# Slider.net
KiCad netlist of a schematic drawn in Altium Designer
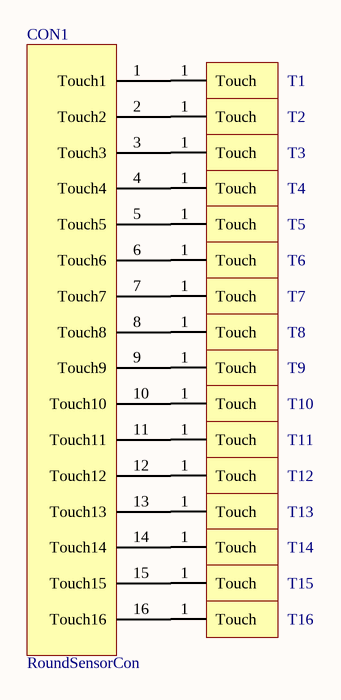
[diagram p0: Slider.SchDoc]

(export (version "E")
  (design (tool "Eeschema 10.0.6"))
  (components
    (comp (ref "CON1")
      (value "RoundSensorCon")
      (footprint "RoundSensorCon")
      (libsource (lib "RoundSensorCon") (part "RoundSensorCon"))
    )
    (comp (ref "T1") (value "Touch") (footprint "TOUCH") (libsource (lib "Touch") (part "Touch")))
    (comp (ref "T2") (value "Touch") (footprint "TOUCH") (libsource (lib "Touch") (part "Touch")))
    (comp (ref "T3") (value "Touch") (footprint "TOUCH") (libsource (lib "Touch") (part "Touch")))
    (comp (ref "T4") (value "Touch") (footprint "TOUCH") (libsource (lib "Touch") (part "Touch")))
    (comp (ref "T5") (value "Touch") (footprint "TOUCH") (libsource (lib "Touch") (part "Touch")))
    (comp (ref "T6") (value "Touch") (footprint "TOUCH") (libsource (lib "Touch") (part "Touch")))
    (comp (ref "T7") (value "Touch") (footprint "TOUCH") (libsource (lib "Touch") (part "Touch")))
    (comp (ref "T8") (value "Touch") (footprint "TOUCH") (libsource (lib "Touch") (part "Touch")))
    (comp (ref "T9") (value "Touch") (footprint "TOUCH") (libsource (lib "Touch") (part "Touch")))
    (comp (ref "T10") (value "Touch") (footprint "TOUCH") (libsource (lib "Touch") (part "Touch")))
    (comp (ref "T11") (value "Touch") (footprint "TOUCH") (libsource (lib "Touch") (part "Touch")))
    (comp (ref "T12") (value "Touch") (footprint "TOUCH") (libsource (lib "Touch") (part "Touch")))
    (comp (ref "T13") (value "Touch") (footprint "TOUCH") (libsource (lib "Touch") (part "Touch")))
    (comp (ref "T14") (value "Touch") (footprint "TOUCH") (libsource (lib "Touch") (part "Touch")))
    (comp (ref "T15") (value "Touch") (footprint "TOUCH") (libsource (lib "Touch") (part "Touch")))
    (comp (ref "T16") (value "Touch") (footprint "TOUCH") (libsource (lib "Touch") (part "Touch")))
  )
  (nets
    (net (code "1") (name "Net-(CON1-Touch1)") (class "Default")
      (node (ref "CON1") (pin "1") (pinfunction "Touch1_1") (pintype "passive"))
      (node (ref "T1") (pin "1") (pinfunction "Touch_1") (pintype "passive"))
    )
    (net (code "2") (name "Net-(CON1-Touch2)") (class "Default")
      (node (ref "CON1") (pin "2") (pinfunction "Touch2_2") (pintype "passive"))
      (node (ref "T2") (pin "1") (pinfunction "Touch_1") (pintype "passive"))
    )
    (net (code "3") (name "Net-(CON1-Touch3)") (class "Default")
      (node (ref "CON1") (pin "3") (pinfunction "Touch3_3") (pintype "passive"))
      (node (ref "T3") (pin "1") (pinfunction "Touch_1") (pintype "passive"))
    )
    (net (code "4") (name "Net-(CON1-Touch4)") (class "Default")
      (node (ref "CON1") (pin "4") (pinfunction "Touch4_4") (pintype "passive"))
      (node (ref "T4") (pin "1") (pinfunction "Touch_1") (pintype "passive"))
    )
    (net (code "5") (name "Net-(CON1-Touch5)") (class "Default")
      (node (ref "CON1") (pin "5") (pinfunction "Touch5_5") (pintype "passive"))
      (node (ref "T5") (pin "1") (pinfunction "Touch_1") (pintype "passive"))
    )
    (net (code "6") (name "Net-(CON1-Touch6)") (class "Default")
      (node (ref "CON1") (pin "6") (pinfunction "Touch6_6") (pintype "passive"))
      (node (ref "T6") (pin "1") (pinfunction "Touch_1") (pintype "passive"))
    )
    (net (code "7") (name "Net-(CON1-Touch7)") (class "Default")
      (node (ref "CON1") (pin "7") (pinfunction "Touch7_7") (pintype "passive"))
      (node (ref "T7") (pin "1") (pinfunction "Touch_1") (pintype "passive"))
    )
    (net (code "8") (name "Net-(CON1-Touch8)") (class "Default")
      (node (ref "CON1") (pin "8") (pinfunction "Touch8_8") (pintype "passive"))
      (node (ref "T8") (pin "1") (pinfunction "Touch_1") (pintype "passive"))
    )
    (net (code "9") (name "Net-(CON1-Touch9)") (class "Default")
      (node (ref "CON1") (pin "9") (pinfunction "Touch9_9") (pintype "passive"))
      (node (ref "T9") (pin "1") (pinfunction "Touch_1") (pintype "passive"))
    )
    (net (code "10") (name "Net-(CON1-Touch10)") (class "Default")
      (node (ref "CON1") (pin "10") (pinfunction "Touch10_10") (pintype "passive"))
      (node (ref "T10") (pin "1") (pinfunction "Touch_1") (pintype "passive"))
    )
    (net (code "11") (name "Net-(CON1-Touch11)") (class "Default")
      (node (ref "CON1") (pin "11") (pinfunction "Touch11_11") (pintype "passive"))
      (node (ref "T11") (pin "1") (pinfunction "Touch_1") (pintype "passive"))
    )
    (net (code "12") (name "Net-(CON1-Touch12)") (class "Default")
      (node (ref "CON1") (pin "12") (pinfunction "Touch12_12") (pintype "passive"))
      (node (ref "T12") (pin "1") (pinfunction "Touch_1") (pintype "passive"))
    )
    (net (code "13") (name "Net-(CON1-Touch13)") (class "Default")
      (node (ref "CON1") (pin "13") (pinfunction "Touch13_13") (pintype "passive"))
      (node (ref "T13") (pin "1") (pinfunction "Touch_1") (pintype "passive"))
    )
    (net (code "14") (name "Net-(CON1-Touch14)") (class "Default")
      (node (ref "CON1") (pin "14") (pinfunction "Touch14_14") (pintype "passive"))
      (node (ref "T14") (pin "1") (pinfunction "Touch_1") (pintype "passive"))
    )
    (net (code "15") (name "Net-(CON1-Touch15)") (class "Default")
      (node (ref "CON1") (pin "15") (pinfunction "Touch15_15") (pintype "passive"))
      (node (ref "T15") (pin "1") (pinfunction "Touch_1") (pintype "passive"))
    )
    (net (code "16") (name "Net-(CON1-Touch16)") (class "Default")
      (node (ref "CON1") (pin "16") (pinfunction "Touch16_16") (pintype "passive"))
      (node (ref "T16") (pin "1") (pinfunction "Touch_1") (pintype "passive"))
    )
  )
)
